# DSC_Arduino_Shield.net
KiCad netlist of a schematic drawn in EAGLE
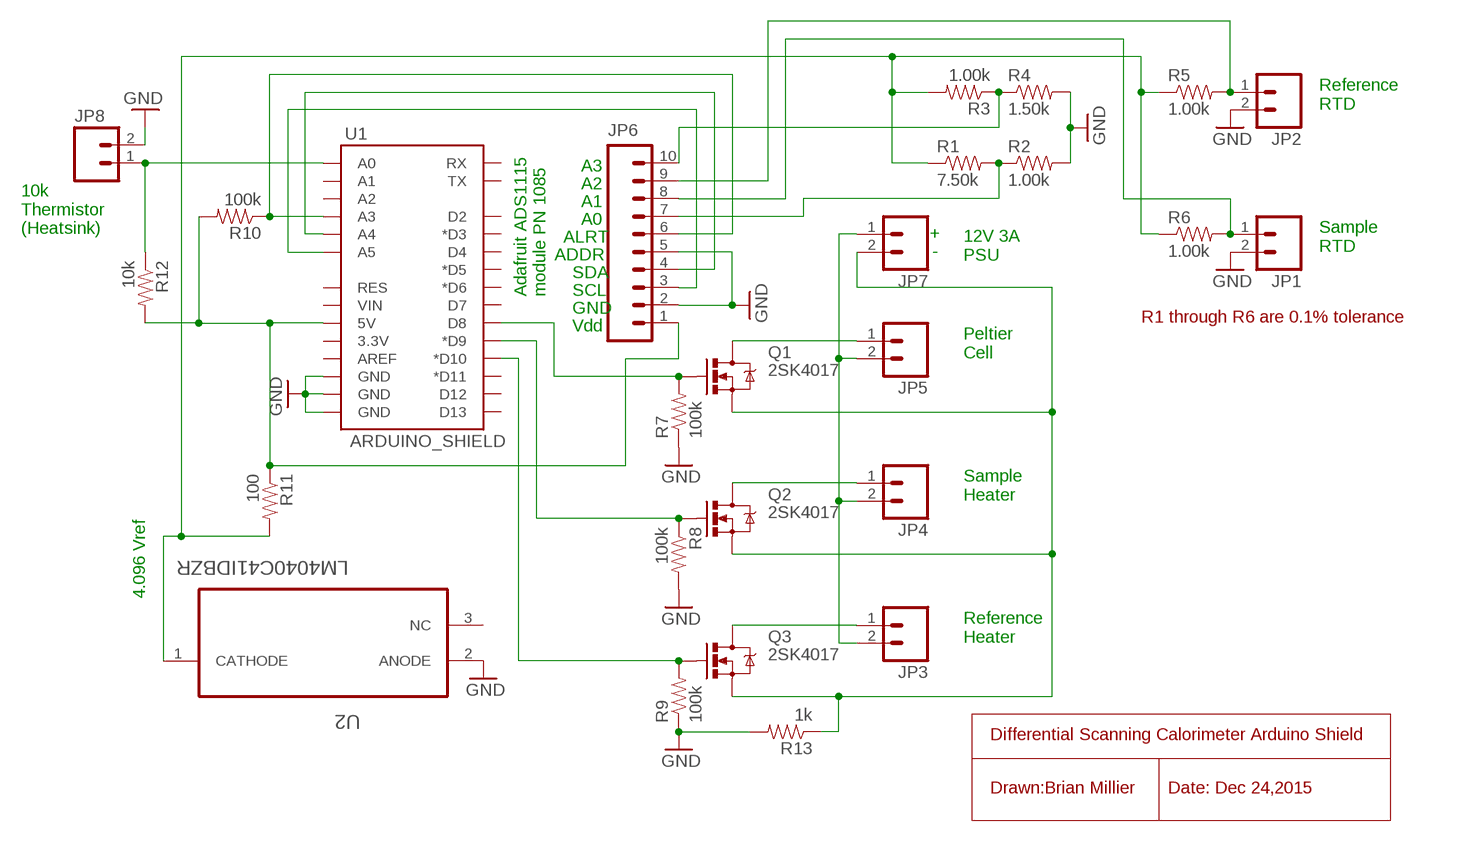
[diagram p0: schematic, sheet 1]

(export (version "E")
  (design (tool "Eeschema 10.0.6"))
  (components
    (comp (ref "JP1")
      (value "M023.5MM_LOCK")
      (footprint "eagle-import:SCREWTERMINAL-3.5MM-2_LOCK")
      (libsource (lib "eagle-import") (part "M023.5MM_LOCK"))
    )
    (comp (ref "JP2")
      (value "M023.5MM_LOCK")
      (footprint "eagle-import:SCREWTERMINAL-3.5MM-2_LOCK")
      (libsource (lib "eagle-import") (part "M023.5MM_LOCK"))
    )
    (comp (ref "JP3")
      (value "M023.5MM_LOCK")
      (footprint "eagle-import:SCREWTERMINAL-3.5MM-2_LOCK")
      (libsource (lib "eagle-import") (part "M023.5MM_LOCK"))
    )
    (comp (ref "JP4")
      (value "M023.5MM_LOCK")
      (footprint "eagle-import:SCREWTERMINAL-3.5MM-2_LOCK")
      (libsource (lib "eagle-import") (part "M023.5MM_LOCK"))
    )
    (comp (ref "JP5")
      (value "M023.5MM_LOCK")
      (footprint "eagle-import:SCREWTERMINAL-3.5MM-2_LOCK")
      (libsource (lib "eagle-import") (part "M023.5MM_LOCK"))
    )
    (comp (ref "JP6")
      (value "M10SILK_FEMALE_PTH")
      (footprint "eagle-import:1X10")
      (libsource (lib "eagle-import") (part "M10SILK_FEMALE_PTH"))
    )
    (comp (ref "JP7")
      (value "M023.5MM_LOCK")
      (footprint "eagle-import:SCREWTERMINAL-3.5MM-2_LOCK")
      (libsource (lib "eagle-import") (part "M023.5MM_LOCK"))
    )
    (comp (ref "JP8")
      (value "M023.5MM_LOCK")
      (footprint "eagle-import:SCREWTERMINAL-3.5MM-2_LOCK")
      (libsource (lib "eagle-import") (part "M023.5MM_LOCK"))
    )
    (comp (ref "Q1")
      (value "2SK4017")
      (footprint "eagle-import:DPAK")
      (libsource (lib "eagle-import") (part "MOSFET-NCHANNELFDD8780"))
    )
    (comp (ref "Q2")
      (value "2SK4017")
      (footprint "eagle-import:DPAK")
      (libsource (lib "eagle-import") (part "MOSFET-NCHANNELFDD8780"))
    )
    (comp (ref "Q3")
      (value "2SK4017")
      (footprint "eagle-import:DPAK")
      (libsource (lib "eagle-import") (part "MOSFET-NCHANNELFDD8780"))
    )
    (comp (ref "R1")
      (value "7.50k")
      (footprint "eagle-import:AXIAL-0.3")
      (libsource (lib "eagle-import") (part "10KOHM-1/4W-1%(PTH)HORIZ"))
    )
    (comp (ref "R2")
      (value "1.00k")
      (footprint "eagle-import:AXIAL-0.3")
      (libsource (lib "eagle-import") (part "10KOHM-1/4W-1%(PTH)HORIZ"))
    )
    (comp (ref "R3")
      (value "1.00k")
      (footprint "eagle-import:AXIAL-0.3")
      (libsource (lib "eagle-import") (part "10KOHM-1/4W-1%(PTH)HORIZ"))
    )
    (comp (ref "R4")
      (value "1.50k")
      (footprint "eagle-import:AXIAL-0.3")
      (libsource (lib "eagle-import") (part "10KOHM-1/4W-1%(PTH)HORIZ"))
    )
    (comp (ref "R5")
      (value "1.00k")
      (footprint "eagle-import:AXIAL-0.3")
      (libsource (lib "eagle-import") (part "10KOHM-1/4W-1%(PTH)HORIZ"))
    )
    (comp (ref "R6")
      (value "1.00k")
      (footprint "eagle-import:AXIAL-0.3")
      (libsource (lib "eagle-import") (part "10KOHM-1/4W-1%(PTH)HORIZ"))
    )
    (comp (ref "R7")
      (value "100k")
      (footprint "eagle-import:AXIAL-0.3")
      (libsource (lib "eagle-import") (part "10KOHM-1/4W-1%(PTH)HORIZ"))
    )
    (comp (ref "R8")
      (value "100k")
      (footprint "eagle-import:AXIAL-0.3")
      (libsource (lib "eagle-import") (part "10KOHM-1/4W-1%(PTH)HORIZ"))
    )
    (comp (ref "R9")
      (value "100k")
      (footprint "eagle-import:AXIAL-0.3")
      (libsource (lib "eagle-import") (part "10KOHM-1/4W-1%(PTH)HORIZ"))
    )
    (comp (ref "R10")
      (value "100k")
      (footprint "eagle-import:AXIAL-0.3")
      (libsource (lib "eagle-import") (part "10KOHM-1/4W-1%(PTH)HORIZ"))
    )
    (comp (ref "R11")
      (value "100")
      (footprint "eagle-import:AXIAL-0.3")
      (libsource (lib "eagle-import") (part "10KOHM-1/4W-1%(PTH)HORIZ"))
    )
    (comp (ref "R12")
      (value "10k")
      (footprint "eagle-import:AXIAL-0.3")
      (libsource (lib "eagle-import") (part "10KOHM-1/4W-1%(PTH)HORIZ"))
    )
    (comp (ref "R13")
      (value "1k")
      (footprint "eagle-import:AXIAL-0.3")
      (libsource (lib "eagle-import") (part "10KOHM-1/4W-1%(PTH)HORIZ"))
    )
    (comp (ref "U1")
      (value "ARDUINO_SHIELD")
      (footprint "eagle-import:DUEMILANOVE_VIAS")
      (libsource (lib "eagle-import") (part "ARDUINO_SHIELDNO_SILK"))
    )
    (comp (ref "U2")
      (value "LM4040C41IDBZR")
      (footprint "eagle-import:SOT95P237X112-3N")
      (libsource (lib "eagle-import") (part "LM4040C41IDBZR"))
    )
  )
  (nets
    (net (code "1") (name "GND") (class "Default")
      (node (ref "JP1") (pin "2") (pinfunction "2_2") (pintype "passive"))
      (node (ref "JP2") (pin "2") (pinfunction "2_2") (pintype "passive"))
      (node (ref "JP6") (pin "2") (pinfunction "2_2") (pintype "passive"))
      (node (ref "JP6") (pin "5") (pinfunction "5_5") (pintype "passive"))
      (node (ref "JP8") (pin "2") (pinfunction "2_2") (pintype "passive"))
      (node (ref "R13") (pin "P$2") (pinfunction "2_P$2") (pintype "passive"))
      (node (ref "R2") (pin "P$2") (pinfunction "2_P$2") (pintype "passive"))
      (node (ref "R4") (pin "P$2") (pinfunction "2_P$2") (pintype "passive"))
      (node (ref "R7") (pin "P$1") (pinfunction "1_P$1") (pintype "passive"))
      (node (ref "R8") (pin "P$2") (pinfunction "2_P$2") (pintype "passive"))
      (node (ref "R9") (pin "P$1") (pinfunction "1_P$1") (pintype "passive"))
      (node (ref "U1") (pin "GND@0") (pinfunction "GND_GND@0") (pintype "bidirectional"))
      (node (ref "U1") (pin "GND@1") (pinfunction "GND_GND@1") (pintype "bidirectional"))
      (node (ref "U1") (pin "GND@2") (pinfunction "GND_GND@2") (pintype "bidirectional"))
      (node (ref "U2") (pin "2") (pinfunction "ANODE_2") (pintype "input"))
    )
    (net (code "2") (name "Net-(JP3-Pad2)") (class "Default")
      (node (ref "JP3") (pin "2") (pinfunction "2_2") (pintype "passive"))
      (node (ref "JP4") (pin "2") (pinfunction "2_2") (pintype "passive"))
      (node (ref "JP5") (pin "2") (pinfunction "2_2") (pintype "passive"))
      (node (ref "JP7") (pin "1") (pinfunction "1_1") (pintype "passive"))
    )
    (net (code "3") (name "Net-(JP6-Pad3)") (class "Default")
      (node (ref "JP6") (pin "3") (pinfunction "3_3") (pintype "passive"))
      (node (ref "U1") (pin "A5") (pinfunction "A5_A5") (pintype "bidirectional"))
    )
    (net (code "4") (name "Net-(JP6-Pad4)") (class "Default")
      (node (ref "JP6") (pin "4") (pinfunction "4_4") (pintype "passive"))
      (node (ref "U1") (pin "A4") (pinfunction "A4_A4") (pintype "bidirectional"))
    )
    (net (code "5") (name "Net-(Q1-D)") (class "Default")
      (node (ref "JP5") (pin "1") (pinfunction "1_1") (pintype "passive"))
      (node (ref "Q1") (pin "4") (pinfunction "D_4") (pintype "passive"))
    )
    (net (code "6") (name "Net-(Q1-G)") (class "Default")
      (node (ref "Q1") (pin "1") (pinfunction "G_1") (pintype "passive"))
      (node (ref "R7") (pin "P$2") (pinfunction "2_P$2") (pintype "passive"))
      (node (ref "U1") (pin "D8") (pinfunction "D8_D8") (pintype "bidirectional"))
    )
    (net (code "7") (name "Net-(Q1-S)") (class "Default")
      (node (ref "JP7") (pin "2") (pinfunction "2_2") (pintype "passive"))
      (node (ref "Q1") (pin "3") (pinfunction "S_3") (pintype "passive"))
      (node (ref "Q2") (pin "3") (pinfunction "S_3") (pintype "passive"))
      (node (ref "Q3") (pin "3") (pinfunction "S_3") (pintype "passive"))
      (node (ref "R13") (pin "P$1") (pinfunction "1_P$1") (pintype "passive"))
    )
    (net (code "8") (name "Net-(Q2-D)") (class "Default")
      (node (ref "JP4") (pin "1") (pinfunction "1_1") (pintype "passive"))
      (node (ref "Q2") (pin "4") (pinfunction "D_4") (pintype "passive"))
    )
    (net (code "9") (name "Net-(Q2-G)") (class "Default")
      (node (ref "Q2") (pin "1") (pinfunction "G_1") (pintype "passive"))
      (node (ref "R8") (pin "P$1") (pinfunction "1_P$1") (pintype "passive"))
      (node (ref "U1") (pin "D9") (pinfunction "*D9_D9") (pintype "bidirectional"))
    )
    (net (code "10") (name "Net-(Q3-D)") (class "Default")
      (node (ref "JP3") (pin "1") (pinfunction "1_1") (pintype "passive"))
      (node (ref "Q3") (pin "4") (pinfunction "D_4") (pintype "passive"))
    )
    (net (code "11") (name "Net-(Q3-G)") (class "Default")
      (node (ref "Q3") (pin "1") (pinfunction "G_1") (pintype "passive"))
      (node (ref "R9") (pin "P$2") (pinfunction "2_P$2") (pintype "passive"))
      (node (ref "U1") (pin "D10") (pinfunction "*D10_D10") (pintype "bidirectional"))
    )
    (net (code "12") (name "Net-(R1-1)") (class "Default")
      (node (ref "R1") (pin "P$1") (pinfunction "1_P$1") (pintype "passive"))
      (node (ref "R11") (pin "P$2") (pinfunction "2_P$2") (pintype "passive"))
      (node (ref "R3") (pin "P$2") (pinfunction "2_P$2") (pintype "passive"))
      (node (ref "R5") (pin "P$1") (pinfunction "1_P$1") (pintype "passive"))
      (node (ref "R6") (pin "P$1") (pinfunction "1_P$1") (pintype "passive"))
      (node (ref "U2") (pin "1") (pinfunction "CATHODE_1") (pintype "output"))
    )
    (net (code "13") (name "Net-(R1-2)") (class "Default")
      (node (ref "JP6") (pin "7") (pinfunction "7_7") (pintype "passive"))
      (node (ref "R1") (pin "P$2") (pinfunction "2_P$2") (pintype "passive"))
      (node (ref "R2") (pin "P$1") (pinfunction "1_P$1") (pintype "passive"))
    )
    (net (code "14") (name "Net-(R3-1)") (class "Default")
      (node (ref "JP6") (pin "10") (pinfunction "10_10") (pintype "passive"))
      (node (ref "R3") (pin "P$1") (pinfunction "1_P$1") (pintype "passive"))
      (node (ref "R4") (pin "P$1") (pinfunction "1_P$1") (pintype "passive"))
    )
    (net (code "15") (name "Net-(R5-2)") (class "Default")
      (node (ref "JP2") (pin "1") (pinfunction "1_1") (pintype "passive"))
      (node (ref "JP6") (pin "9") (pinfunction "9_9") (pintype "passive"))
      (node (ref "R5") (pin "P$2") (pinfunction "2_P$2") (pintype "passive"))
    )
    (net (code "16") (name "Net-(R6-2)") (class "Default")
      (node (ref "JP1") (pin "1") (pinfunction "1_1") (pintype "passive"))
      (node (ref "JP6") (pin "8") (pinfunction "8_8") (pintype "passive"))
      (node (ref "R6") (pin "P$2") (pinfunction "2_P$2") (pintype "passive"))
    )
    (net (code "17") (name "Net-(R10-1)") (class "Default")
      (node (ref "JP6") (pin "6") (pinfunction "6_6") (pintype "passive"))
      (node (ref "R10") (pin "P$1") (pinfunction "1_P$1") (pintype "passive"))
      (node (ref "U1") (pin "A3") (pinfunction "A3_A3") (pintype "bidirectional"))
    )
    (net (code "18") (name "Net-(R10-2)") (class "Default")
      (node (ref "JP6") (pin "1") (pinfunction "1_1") (pintype "passive"))
      (node (ref "R10") (pin "P$2") (pinfunction "2_P$2") (pintype "passive"))
      (node (ref "R11") (pin "P$1") (pinfunction "1_P$1") (pintype "passive"))
      (node (ref "R12") (pin "P$2") (pinfunction "2_P$2") (pintype "passive"))
      (node (ref "U1") (pin "5V") (pinfunction "5V_5V") (pintype "bidirectional"))
    )
    (net (code "19") (name "Net-(R12-1)") (class "Default")
      (node (ref "JP8") (pin "1") (pinfunction "1_1") (pintype "passive"))
      (node (ref "R12") (pin "P$1") (pinfunction "1_P$1") (pintype "passive"))
      (node (ref "U1") (pin "A0") (pinfunction "A0_A0") (pintype "bidirectional"))
    )
    (net (code "20") (name "unconnected-(U1-*D3-PadD3)") (class "Default")
      (node (ref "U1") (pin "D3") (pinfunction "*D3_D3") (pintype "bidirectional"))
    )
    (net (code "21") (name "unconnected-(U1-*D5-PadD5)") (class "Default")
      (node (ref "U1") (pin "D5") (pinfunction "*D5_D5") (pintype "bidirectional"))
    )
    (net (code "22") (name "unconnected-(U1-*D6-PadD6)") (class "Default")
      (node (ref "U1") (pin "D6") (pinfunction "*D6_D6") (pintype "bidirectional"))
    )
    (net (code "23") (name "unconnected-(U1-*D11-PadD11)") (class "Default")
      (node (ref "U1") (pin "D11") (pinfunction "*D11_D11") (pintype "bidirectional"))
    )
    (net (code "24") (name "unconnected-(U1-Pad3.3V)") (class "Default")
      (node (ref "U1") (pin "3.3V") (pinfunction "3.3V_3.3V") (pintype "bidirectional"))
    )
    (net (code "25") (name "unconnected-(U1-PadA1)") (class "Default")
      (node (ref "U1") (pin "A1") (pinfunction "A1_A1") (pintype "bidirectional"))
    )
    (net (code "26") (name "unconnected-(U1-PadA2)") (class "Default")
      (node (ref "U1") (pin "A2") (pinfunction "A2_A2") (pintype "bidirectional"))
    )
    (net (code "27") (name "unconnected-(U1-PadAREF)") (class "Default")
      (node (ref "U1") (pin "AREF") (pinfunction "AREF_AREF") (pintype "bidirectional"))
    )
    (net (code "28") (name "unconnected-(U1-PadD2)") (class "Default")
      (node (ref "U1") (pin "D2") (pinfunction "D2_D2") (pintype "bidirectional"))
    )
    (net (code "29") (name "unconnected-(U1-PadD4)") (class "Default")
      (node (ref "U1") (pin "D4") (pinfunction "D4_D4") (pintype "bidirectional"))
    )
    (net (code "30") (name "unconnected-(U1-PadD7)") (class "Default")
      (node (ref "U1") (pin "D7") (pinfunction "D7_D7") (pintype "bidirectional"))
    )
    (net (code "31") (name "unconnected-(U1-PadD12)") (class "Default")
      (node (ref "U1") (pin "D12") (pinfunction "D12_D12") (pintype "bidirectional"))
    )
    (net (code "32") (name "unconnected-(U1-PadD13)") (class "Default")
      (node (ref "U1") (pin "D13") (pinfunction "D13_D13") (pintype "bidirectional"))
    )
    (net (code "33") (name "unconnected-(U1-PadRES)") (class "Default")
      (node (ref "U1") (pin "RES") (pinfunction "RES_RES") (pintype "bidirectional"))
    )
    (net (code "34") (name "unconnected-(U1-PadRX)") (class "Default")
      (node (ref "U1") (pin "RX") (pinfunction "RX_RX") (pintype "bidirectional"))
    )
    (net (code "35") (name "unconnected-(U1-PadTX)") (class "Default")
      (node (ref "U1") (pin "TX") (pinfunction "TX_TX") (pintype "bidirectional"))
    )
    (net (code "36") (name "unconnected-(U1-PadVIN)") (class "Default")
      (node (ref "U1") (pin "VIN") (pinfunction "VIN_VIN") (pintype "bidirectional"))
    )
    (net (code "37") (name "unconnected-(U2-NC-Pad3)") (class "Default")
      (node (ref "U2") (pin "3") (pinfunction "NC_3") (pintype "no_connect"))
    )
  )
)
